# head.net
KiCad netlist of a schematic drawn in EAGLE
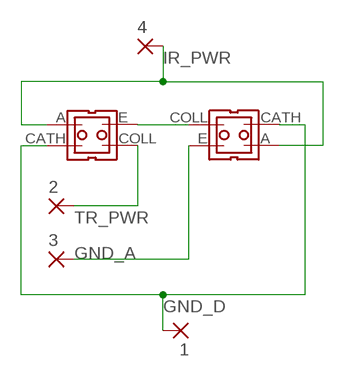
[diagram p0: schematic, sheet 1]

(export (version "E")
  (design (tool "Eeschema 10.0.6"))
  (components
    (comp (ref "1")
      (value "2,15/1,0")
      (footprint "eagle-import:2,15_1,0")
      (libsource (lib "eagle-import") (part "2,15/1,0"))
    )
    (comp (ref "2")
      (value "2,15/1,0")
      (footprint "eagle-import:2,15_1,0")
      (libsource (lib "eagle-import") (part "2,15/1,0"))
    )
    (comp (ref "3")
      (value "2,15/1,0")
      (footprint "eagle-import:2,15_1,0")
      (libsource (lib "eagle-import") (part "2,15/1,0"))
    )
    (comp (ref "4")
      (value "2,15/1,0")
      (footprint "eagle-import:2,15_1,0")
      (libsource (lib "eagle-import") (part "2,15/1,0"))
    )
    (comp (ref "U$1")
      (value "CNY70")
      (footprint "eagle-import:CNY70")
      (libsource (lib "eagle-import") (part "CNY70"))
    )
    (comp (ref "U$2")
      (value "CNY70")
      (footprint "eagle-import:CNY70")
      (libsource (lib "eagle-import") (part "CNY70"))
    )
  )
  (nets
    (net (code "1") (name "/GND_A") (class "Default")
      (node (ref "3") (pin "1") (pinfunction "P_1") (pintype "passive"))
      (node (ref "U$2") (pin "E") (pinfunction "GND(PWR)_E") (pintype "power_in"))
    )
    (net (code "2") (name "/GND_D") (class "Default")
      (node (ref "1") (pin "1") (pinfunction "P_1") (pintype "passive"))
      (node (ref "U$1") (pin "CATH") (pinfunction "GND(DIG)_CATH") (pintype "power_in"))
      (node (ref "U$2") (pin "CATH") (pinfunction "GND(DIG)_CATH") (pintype "power_in"))
    )
    (net (code "3") (name "/IR_PWR") (class "Default")
      (node (ref "4") (pin "1") (pinfunction "P_1") (pintype "passive"))
      (node (ref "U$1") (pin "A") (pinfunction "5V(DIG)_A") (pintype "power_in"))
      (node (ref "U$2") (pin "A") (pinfunction "5V(DIG)_A") (pintype "power_in"))
    )
    (net (code "4") (name "/TR_PWR") (class "Default")
      (node (ref "2") (pin "1") (pinfunction "P_1") (pintype "passive"))
      (node (ref "U$1") (pin "COLL") (pinfunction "5V(PWR)_COLL") (pintype "power_in"))
    )
    (net (code "5") (name "Net-(U$1-GND(PWR))") (class "Default")
      (node (ref "U$1") (pin "E") (pinfunction "GND(PWR)_E") (pintype "power_in"))
      (node (ref "U$2") (pin "COLL") (pinfunction "5V(PWR)_COLL") (pintype "power_in"))
    )
  )
)
